# KeeWatch_Sensors.net
KiCad netlist of a schematic drawn in Altium Designer
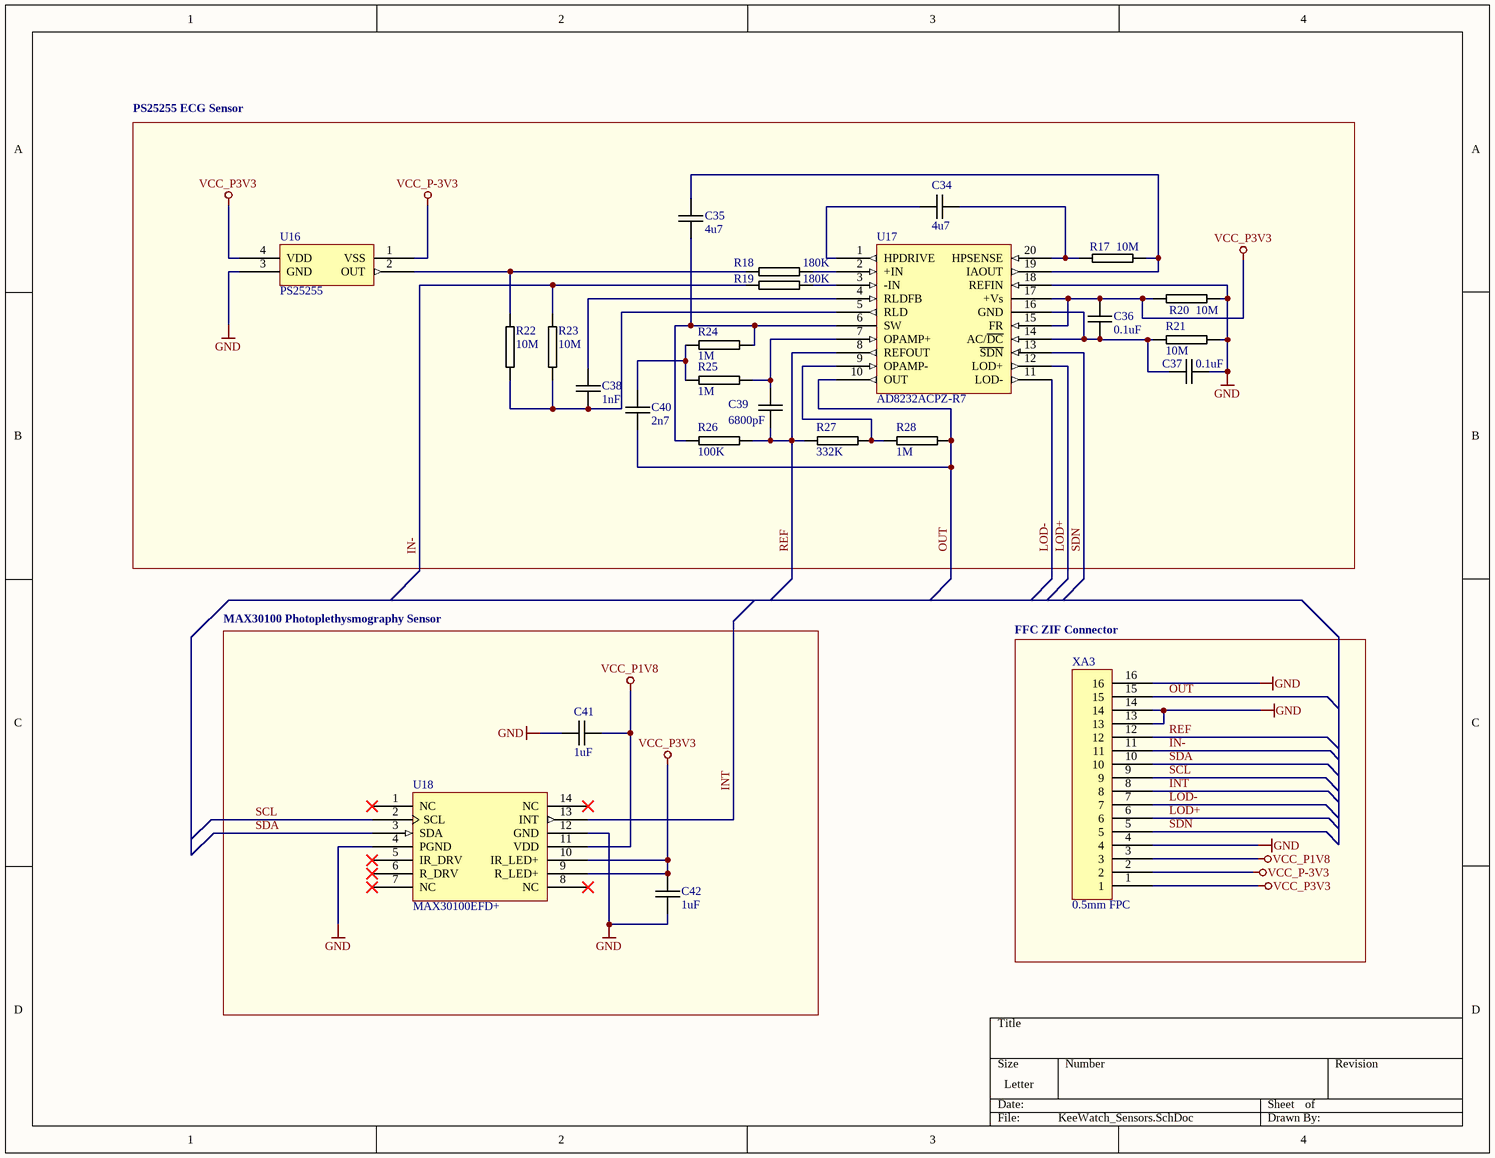
[diagram p0: KeeWatch_Sensors.SchDoc]

(export (version "E")
  (design (tool "Eeschema 10.0.6"))
  (components
    (comp (ref "C34")
      (value "4u7")
      (footprint "0402C-GENERIC")
      (description "CAPACITOR 0402 CERAMIC")
      (libsource (lib "vh_altium_library") (part "0402C-4U7-10V-X5R-SAM"))
    )
    (comp (ref "C35")
      (value "4u7")
      (footprint "0402C-GENERIC")
      (description "CAPACITOR 0402 CERAMIC")
      (libsource (lib "vh_altium_library") (part "0402C-4U7-10V-X5R-SAM"))
    )
    (comp (ref "C36")
      (value "0.1uF")
      (footprint "0603C-GENERIC")
      (description "CAPACITOR 0603 CERAMIC")
      (fields
        (field (name "MANUFACTURER") "TDK Corporation")
        (field (name "MANUFACTURER PART NUMBER") "C1608X5R1A105K")
      )
      (libsource (lib "vh_altium_library") (part "0603C-1UF-10V-X5R-TDK"))
    )
    (comp (ref "C37")
      (value "0.1uF")
      (footprint "0603C-GENERIC")
      (description "CAPACITOR 0603 CERAMIC")
      (fields
        (field (name "MANUFACTURER") "TDK Corporation")
        (field (name "MANUFACTURER PART NUMBER") "C1608X5R1A105K")
      )
      (libsource (lib "vh_altium_library") (part "0603C-1UF-10V-X5R-TDK"))
    )
    (comp (ref "C38")
      (value "1nF")
      (footprint "0603C-GENERIC")
      (description "CAPACITOR 0603 CERAMIC")
      (libsource (lib "vh_altium_library") (part "0603C-1NF-50V-X7R"))
    )
    (comp (ref "C39")
      (value "6800pF")
      (footprint "0603C-GENERIC")
      (description "CAPACITOR 0603 CERAMIC")
      (libsource (lib "vh_altium_library") (part "0603C-3900pF"))
    )
    (comp (ref "C40")
      (value "2n7")
      (footprint "0603C-GENERIC")
      (description "CAPACITOR 0603 CERAMIC")
      (libsource (lib "vh_altium_library") (part "0603C-4P7-50V-NP0"))
    )
    (comp (ref "C41")
      (value "1uF")
      (footprint "0603C-GENERIC")
      (description "CAPACITOR 0603 CERAMIC")
      (fields
        (field (name "MANUFACTURER") "TDK Corporation")
        (field (name "MANUFACTURER PART NUMBER") "C1608X5R1A105K")
      )
      (libsource (lib "vh_altium_library") (part "0603C-1UF-10V-X5R-TDK"))
    )
    (comp (ref "C42")
      (value "1uF")
      (footprint "0603C-GENERIC")
      (description "CAPACITOR 0603 CERAMIC")
      (fields
        (field (name "MANUFACTURER") "TDK Corporation")
        (field (name "MANUFACTURER PART NUMBER") "C1608X5R1A105K")
      )
      (libsource (lib "vh_altium_library") (part "0603C-1UF-10V-X5R-TDK"))
    )
    (comp (ref "R17")
      (value "10M")
      (footprint "0603R-GENERIC")
      (description "GENERIC RESISTOR 0603")
      (fields (field (name "TOLERANCE") "±5%") (field (name "MANUFACTURER PART NUMBER") "RMCF 1/16 10M 5% R"))
      (libsource (lib "vh_altium_library") (part "0603R-10M"))
    )
    (comp (ref "R18")
      (value "180K")
      (footprint "0603R-180K")
      (description "GENERIC RESISTOR 0603")
      (fields
        (field (name "MANUFACTURER PART NUMBER") "RMC 1/16 180K 1% R")
        (field (name "MANUFACTURER") "Stackpole Electronics Inc")
      )
      (libsource (lib "vh_altium_library") (part "0603R-180K"))
    )
    (comp (ref "R19")
      (value "180K")
      (footprint "0603R-180K")
      (description "GENERIC RESISTOR 0603")
      (fields
        (field (name "MANUFACTURER PART NUMBER") "RMC 1/16 180K 1% R")
        (field (name "MANUFACTURER") "Stackpole Electronics Inc")
      )
      (libsource (lib "vh_altium_library") (part "0603R-180K"))
    )
    (comp (ref "R20")
      (value "10M")
      (footprint "0603R-GENERIC")
      (description "GENERIC RESISTOR 0603")
      (fields (field (name "TOLERANCE") "±5%") (field (name "MANUFACTURER PART NUMBER") "RMCF 1/16 10M 5% R"))
      (libsource (lib "vh_altium_library") (part "0603R-10M"))
    )
    (comp (ref "R21")
      (value "10M")
      (footprint "0603R-GENERIC")
      (description "GENERIC RESISTOR 0603")
      (fields (field (name "TOLERANCE") "±5%") (field (name "MANUFACTURER PART NUMBER") "RMCF 1/16 10M 5% R"))
      (libsource (lib "vh_altium_library") (part "0603R-10M"))
    )
    (comp (ref "R22")
      (value "10M")
      (footprint "0603R-GENERIC")
      (description "GENERIC RESISTOR 0603")
      (fields (field (name "TOLERANCE") "±5%") (field (name "MANUFACTURER PART NUMBER") "RMCF 1/16 10M 5% R"))
      (libsource (lib "vh_altium_library") (part "0603R-10M"))
    )
    (comp (ref "R23")
      (value "10M")
      (footprint "0603R-GENERIC")
      (description "GENERIC RESISTOR 0603")
      (fields (field (name "TOLERANCE") "±5%") (field (name "MANUFACTURER PART NUMBER") "RMCF 1/16 10M 5% R"))
      (libsource (lib "vh_altium_library") (part "0603R-10M"))
    )
    (comp (ref "R24")
      (value "1M")
      (footprint "0603R-GENERIC")
      (description "GENERIC RESISTOR 0603")
      (fields
        (field (name "MANUFACTURER") "Stackpole Electronics Inc")
        (field (name "MANUFACTURER PART NUMBER") "RMCF 1/16 1M 1% R")
      )
      (libsource (lib "vh_altium_library") (part "0603R-1M"))
    )
    (comp (ref "R25")
      (value "1M")
      (footprint "0603R-GENERIC")
      (description "GENERIC RESISTOR 0603")
      (fields
        (field (name "MANUFACTURER") "Stackpole Electronics Inc")
        (field (name "MANUFACTURER PART NUMBER") "RMCF 1/16 1M 1% R")
      )
      (libsource (lib "vh_altium_library") (part "0603R-1M"))
    )
    (comp (ref "R26")
      (value "100K")
      (footprint "0603R-100K")
      (description "GENERIC RESISTOR 0603")
      (fields
        (field (name "TOLERANCE") "±1%")
        (field (name "MANUFACTURER PART NUMBER") "RMCF 1/16 100K 1% R")
      )
      (libsource (lib "vh_altium_library") (part "0603R-100K"))
    )
    (comp (ref "R27")
      (value "332K")
      (footprint "0603R-330K")
      (description "GENERIC RESISTOR 0603")
      (fields
        (field (name "MANUFACTURER") "Stackpole Electronics Inc")
        (field (name "MANUFACTURER PART NUMBER") "RMCF 1/16 330K 1% R")
      )
      (libsource (lib "vh_altium_library") (part "0603R-330K"))
    )
    (comp (ref "R28")
      (value "1M")
      (footprint "0603R-GENERIC")
      (description "GENERIC RESISTOR 0603")
      (fields
        (field (name "MANUFACTURER") "Stackpole Electronics Inc")
        (field (name "MANUFACTURER PART NUMBER") "RMCF 1/16 1M 1% R")
      )
      (libsource (lib "vh_altium_library") (part "0603R-1M"))
    )
    (comp (ref "U16")
      (value "PS25255")
      (footprint "PS25255")
      (description "EPIC Ultra High Impedance ECG Senso")
      (libsource (lib "WATCH") (part "PS25255"))
    )
    (comp (ref "U17")
      (value "AD8232ACPZ-R7")
      (footprint "LFCSP_WQ20")
      (description "Single-Lead, Heart Rate Monitor Front End")
      (libsource (lib "WATCH") (part "AD8232ACPZ-R7"))
    )
    (comp (ref "U18")
      (value "MAX30100EFD+")
      (footprint "14OESIP")
      (description "Pulse Oximeter and Heart-Rate Sensor IC for Wearable Health")
      (libsource (lib "WATCH") (part "MAX30100EFD+"))
    )
    (comp (ref "XA3")
      (value "0.5mm FPC")
      (footprint "16-PIN CONNECTOR")
      (description "0.5mm FPC 16-pin Connector")
      (libsource (lib "WATCH") (part "0.5mm FPC"))
    )
  )
  (nets
    (net (code "1") (name "/IN-") (class "Default")
      (node (ref "R19") (pin "1") (pintype "passive"))
      (node (ref "R23") (pin "2") (pintype "passive"))
      (node (ref "XA3") (pin "11") (pinfunction "11_11") (pintype "passive"))
    )
    (net (code "2") (name "/INT") (class "Default")
      (node (ref "U18") (pin "13") (pinfunction "INT_13") (pintype "output"))
      (node (ref "XA3") (pin "8") (pinfunction "8_8") (pintype "passive"))
    )
    (net (code "3") (name "/LOD+") (class "Default")
      (node (ref "U17") (pin "12") (pinfunction "LOD+_12") (pintype "output"))
      (node (ref "XA3") (pin "6") (pinfunction "6_6") (pintype "passive"))
    )
    (net (code "4") (name "/LOD-") (class "Default")
      (node (ref "U17") (pin "11") (pinfunction "LOD-_11") (pintype "output"))
      (node (ref "XA3") (pin "7") (pinfunction "7_7") (pintype "passive"))
    )
    (net (code "5") (name "/OUT") (class "Default")
      (node (ref "C40") (pin "2") (pintype "passive"))
      (node (ref "R28") (pin "1") (pintype "passive"))
      (node (ref "U17") (pin "10") (pinfunction "OUT_10") (pintype "output"))
      (node (ref "XA3") (pin "15") (pinfunction "15_15") (pintype "passive"))
    )
    (net (code "6") (name "/REF") (class "Default")
      (node (ref "C39") (pin "2") (pintype "passive"))
      (node (ref "R26") (pin "2") (pintype "passive"))
      (node (ref "R27") (pin "2") (pintype "passive"))
      (node (ref "U17") (pin "8") (pinfunction "REFOUT_8") (pintype "output"))
      (node (ref "XA3") (pin "12") (pinfunction "12_12") (pintype "passive"))
    )
    (net (code "7") (name "/SCL") (class "Default")
      (node (ref "U18") (pin "2") (pinfunction "SCL_2") (pintype "passive"))
      (node (ref "XA3") (pin "9") (pinfunction "9_9") (pintype "passive"))
    )
    (net (code "8") (name "/SDA") (class "Default")
      (node (ref "U18") (pin "3") (pinfunction "SDA_3") (pintype "input"))
      (node (ref "XA3") (pin "10") (pinfunction "10_10") (pintype "passive"))
    )
    (net (code "9") (name "/SDN") (class "Default")
      (node (ref "U17") (pin "13") (pinfunction "~{SDN}_13") (pintype "input"))
      (node (ref "XA3") (pin "5") (pinfunction "5_5") (pintype "passive"))
    )
    (net (code "10") (name "GND") (class "Default")
      (node (ref "C37") (pin "2") (pintype "passive"))
      (node (ref "C41") (pin "1") (pintype "passive"))
      (node (ref "C42") (pin "1") (pintype "passive"))
      (node (ref "R20") (pin "2") (pintype "passive"))
      (node (ref "R21") (pin "2") (pintype "passive"))
      (node (ref "U16") (pin "3") (pinfunction "GND_3") (pintype "passive"))
      (node (ref "U17") (pin "18") (pinfunction "REFIN_18") (pintype "input"))
      (node (ref "U18") (pin "12") (pinfunction "GND_12") (pintype "passive"))
      (node (ref "U18") (pin "4") (pinfunction "PGND_4") (pintype "passive"))
      (node (ref "XA3") (pin "13") (pinfunction "13_13") (pintype "passive"))
      (node (ref "XA3") (pin "14") (pinfunction "14_14") (pintype "passive"))
      (node (ref "XA3") (pin "16") (pinfunction "16_16") (pintype "passive"))
      (node (ref "XA3") (pin "4") (pinfunction "4_4") (pintype "passive"))
    )
    (net (code "11") (name "Net-(C40-Pad1)") (class "Default")
      (node (ref "C40") (pin "1") (pintype "passive"))
      (node (ref "R24") (pin "2") (pintype "passive"))
      (node (ref "R25") (pin "1") (pintype "passive"))
    )
    (net (code "12") (name "Net-(U16-OUT)") (class "Default")
      (node (ref "R18") (pin "1") (pintype "passive"))
      (node (ref "R22") (pin "2") (pintype "passive"))
      (node (ref "U16") (pin "2") (pinfunction "OUT_2") (pintype "output"))
    )
    (net (code "13") (name "Net-(U17-+IN)") (class "Default")
      (node (ref "R18") (pin "2") (pintype "passive"))
      (node (ref "U17") (pin "2") (pinfunction "+IN_2") (pintype "input"))
    )
    (net (code "14") (name "Net-(U17--IN)") (class "Default")
      (node (ref "R19") (pin "2") (pintype "passive"))
      (node (ref "U17") (pin "3") (pinfunction "-IN_3") (pintype "input"))
    )
    (net (code "15") (name "Net-(U17-AC{slash}~{DC})") (class "Default")
      (node (ref "C36") (pin "2") (pintype "passive"))
      (node (ref "C37") (pin "1") (pintype "passive"))
      (node (ref "R21") (pin "1") (pintype "passive"))
      (node (ref "U17") (pin "14") (pinfunction "AC/~{DC}_14") (pintype "input"))
      (node (ref "U17") (pin "16") (pinfunction "GND_16") (pintype "passive"))
    )
    (net (code "16") (name "Net-(U17-HPDRIVE)") (class "Default")
      (node (ref "C34") (pin "1") (pintype "passive"))
      (node (ref "U17") (pin "1") (pinfunction "HPDRIVE_1") (pintype "output"))
    )
    (net (code "17") (name "Net-(U17-HPSENSE)") (class "Default")
      (node (ref "C34") (pin "2") (pintype "passive"))
      (node (ref "R17") (pin "1") (pintype "passive"))
      (node (ref "U17") (pin "20") (pinfunction "HPSENSE_20") (pintype "input"))
    )
    (net (code "18") (name "Net-(U17-IAOUT)") (class "Default")
      (node (ref "C35") (pin "2") (pintype "passive"))
      (node (ref "R17") (pin "2") (pintype "passive"))
      (node (ref "U17") (pin "19") (pinfunction "IAOUT_19") (pintype "output"))
    )
    (net (code "19") (name "Net-(U17-OPAMP+)") (class "Default")
      (node (ref "C39") (pin "1") (pintype "passive"))
      (node (ref "R25") (pin "2") (pintype "passive"))
      (node (ref "U17") (pin "7") (pinfunction "OPAMP+_7") (pintype "input"))
    )
    (net (code "20") (name "Net-(U17-OPAMP-)") (class "Default")
      (node (ref "R27") (pin "1") (pintype "passive"))
      (node (ref "R28") (pin "2") (pintype "passive"))
      (node (ref "U17") (pin "9") (pinfunction "OPAMP-_9") (pintype "input"))
    )
    (net (code "21") (name "Net-(U17-RLD)") (class "Default")
      (node (ref "C38") (pin "2") (pintype "passive"))
      (node (ref "R22") (pin "1") (pintype "passive"))
      (node (ref "R23") (pin "1") (pintype "passive"))
      (node (ref "U17") (pin "5") (pinfunction "RLD_5") (pintype "output"))
    )
    (net (code "22") (name "Net-(U17-RLDFB)") (class "Default")
      (node (ref "C38") (pin "1") (pintype "passive"))
      (node (ref "U17") (pin "4") (pinfunction "RLDFB_4") (pintype "input"))
    )
    (net (code "23") (name "Net-(U17-SW)") (class "Default")
      (node (ref "C35") (pin "1") (pintype "passive"))
      (node (ref "R24") (pin "1") (pintype "passive"))
      (node (ref "R26") (pin "1") (pintype "passive"))
      (node (ref "U17") (pin "6") (pinfunction "SW_6") (pintype "passive"))
    )
    (net (code "24") (name "VCC_P-3V3") (class "Default")
      (node (ref "U16") (pin "1") (pinfunction "VSS_1") (pintype "power_in"))
      (node (ref "XA3") (pin "2") (pinfunction "2_2") (pintype "passive"))
    )
    (net (code "25") (name "VCC_P1V8") (class "Default")
      (node (ref "C41") (pin "2") (pintype "passive"))
      (node (ref "U18") (pin "11") (pinfunction "VDD_11") (pintype "power_in"))
      (node (ref "XA3") (pin "3") (pinfunction "3_3") (pintype "passive"))
    )
    (net (code "26") (name "VCC_P3V3") (class "Default")
      (node (ref "C36") (pin "1") (pintype "passive"))
      (node (ref "C42") (pin "2") (pintype "passive"))
      (node (ref "R20") (pin "1") (pintype "passive"))
      (node (ref "U16") (pin "4") (pinfunction "VDD_4") (pintype "passive"))
      (node (ref "U17") (pin "15") (pinfunction "FR_15") (pintype "input"))
      (node (ref "U17") (pin "17") (pinfunction "+Vs_17") (pintype "power_in"))
      (node (ref "U18") (pin "10") (pinfunction "IR_LED+_10") (pintype "power_in"))
      (node (ref "U18") (pin "9") (pinfunction "R_LED+_9") (pintype "power_in"))
      (node (ref "XA3") (pin "1") (pinfunction "1_1") (pintype "passive"))
    )
    (net (code "27") (name "unconnected-(U18-IR_DRV-Pad5)") (class "Default")
      (node (ref "U18") (pin "5") (pinfunction "IR_DRV_5") (pintype "passive+no_connect"))
    )
    (net (code "28") (name "unconnected-(U18-NC-Pad1)") (class "Default")
      (node (ref "U18") (pin "1") (pinfunction "NC_1") (pintype "passive+no_connect"))
    )
    (net (code "29") (name "unconnected-(U18-NC-Pad7)") (class "Default")
      (node (ref "U18") (pin "7") (pinfunction "NC_7") (pintype "passive+no_connect"))
    )
    (net (code "30") (name "unconnected-(U18-NC-Pad8)") (class "Default")
      (node (ref "U18") (pin "8") (pinfunction "NC_8") (pintype "passive+no_connect"))
    )
    (net (code "31") (name "unconnected-(U18-NC-Pad14)") (class "Default")
      (node (ref "U18") (pin "14") (pinfunction "NC_14") (pintype "passive+no_connect"))
    )
    (net (code "32") (name "unconnected-(U18-R_DRV-Pad6)") (class "Default")
      (node (ref "U18") (pin "6") (pinfunction "R_DRV_6") (pintype "passive+no_connect"))
    )
  )
)
